# SCH_schematic-alarm_2025-03-28.net
KiCad netlist of a schematic drawn in EasyEDA
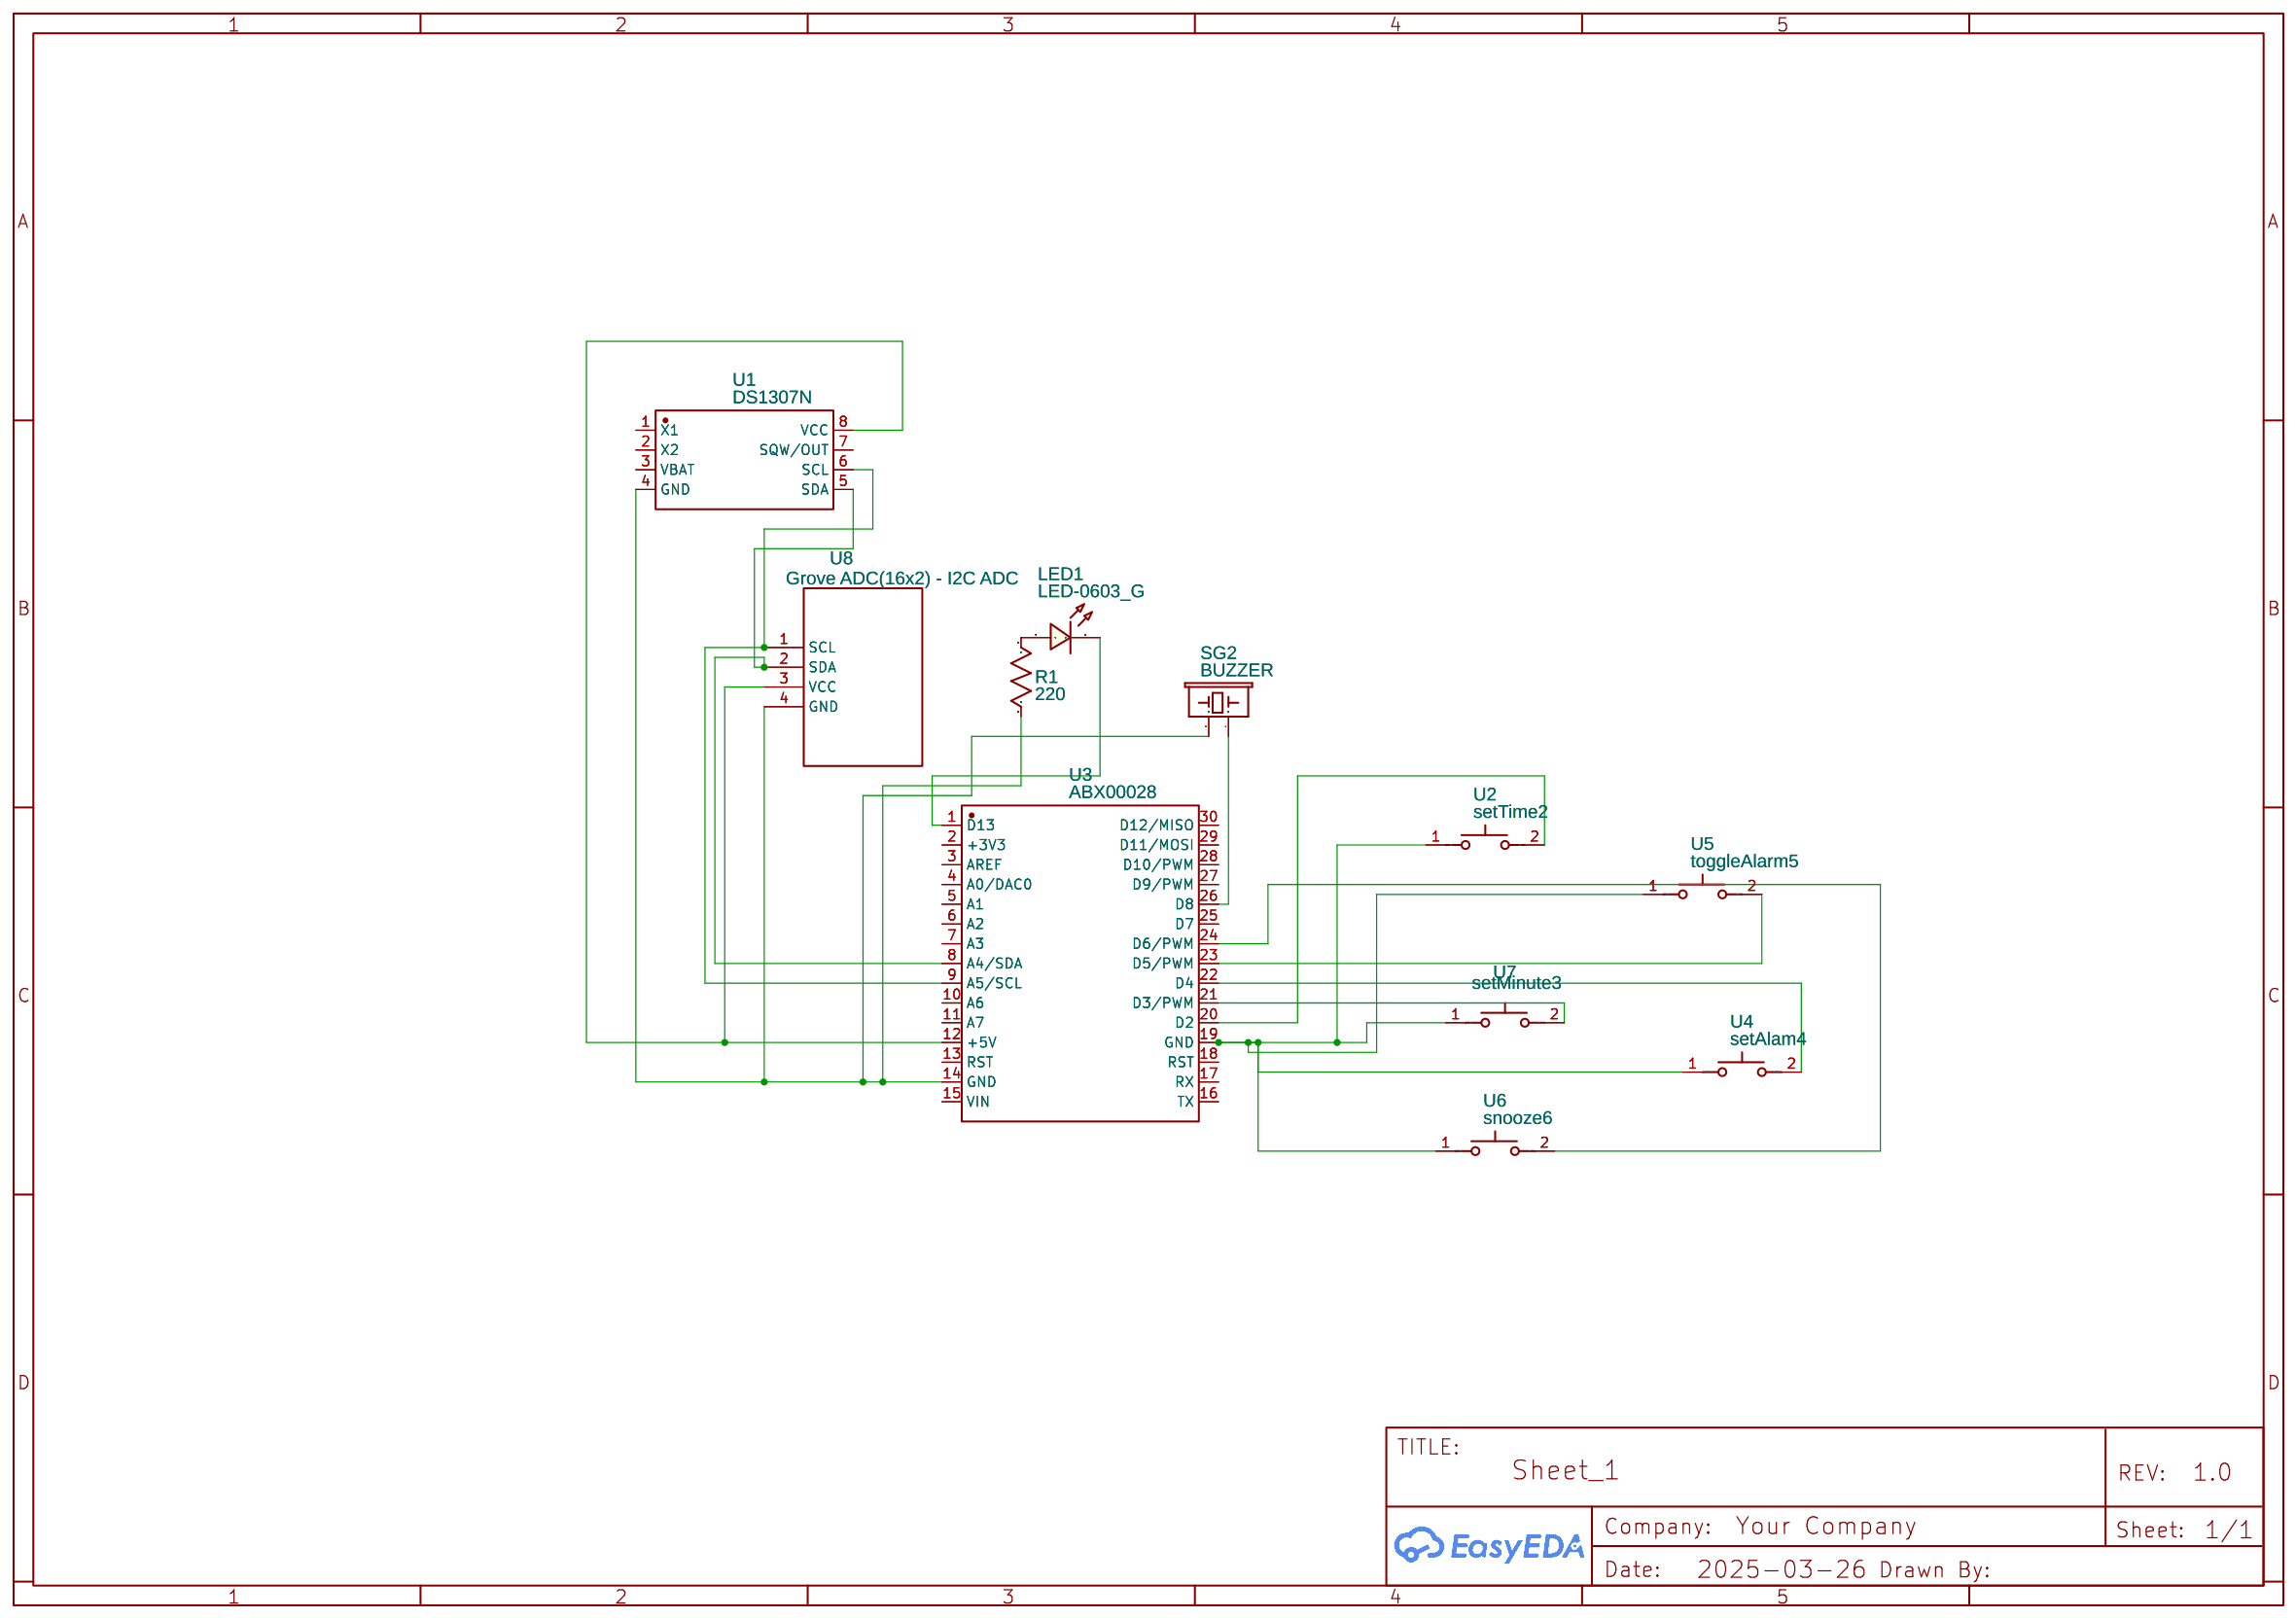
[diagram p0: schematic sheet]

(export (version "E")
  (design (tool "Eeschema 10.0.6"))
  (components
    (comp (ref "LED1")
      (value "LED-0603_G")
      (fields
        (field (name "Manufacturer Part") "19-217/GHC-YR1S2/3T")
        (field (name "Manufacturer") "EVERLIGHT(台湾亿光)")
      )
      (libsource (lib "") (part "LED-0603_G"))
    )
    (comp (ref "R1") (value "220") (libsource (lib "") (part "R_0603_US")))
    (comp (ref "SG2") (value "BUZZER") (libsource (lib "") (part "BUZZER")))
    (comp (ref "U1")
      (value "DS1307N")
      (fields (field (name "Manufacturer") "HGSEMI(华冠)"))
      (libsource (lib "") (part "DS1307N"))
    )
    (comp (ref "U2")
      (value "setTime2")
      (fields (field (name "Manufacturer Part") "BUTTON2"))
      (libsource (lib "") (part "BUTTON2"))
    )
    (comp (ref "U3")
      (value "ABX00028")
      (fields (field (name "Manufacturer") "arduino"))
      (libsource (lib "") (part "ABX00028"))
    )
    (comp (ref "U4")
      (value "setAlam4")
      (fields (field (name "Manufacturer Part") "BUTTON2"))
      (libsource (lib "") (part "BUTTON2"))
    )
    (comp (ref "U5")
      (value "toggleAlarm5")
      (fields (field (name "Manufacturer Part") "BUTTON2"))
      (libsource (lib "") (part "BUTTON2"))
    )
    (comp (ref "U6")
      (value "snooze6")
      (fields (field (name "Manufacturer Part") "BUTTON2"))
      (libsource (lib "") (part "BUTTON2"))
    )
    (comp (ref "U7")
      (value "setMinute3")
      (fields (field (name "Manufacturer Part") "BUTTON2"))
      (libsource (lib "") (part "BUTTON2"))
    )
    (comp (ref "U8") (value "Grove ADC(16x2) - I2C ADC") (libsource (lib "") (part "Grove - I2C ADC")))
  )
  (nets
    (net (code "1") (name "Net-(LED1-Pad1)") (class "Default")
      (node (ref "LED1") (pin "1") (pinfunction "1_1") (pintype "unspecified"))
      (node (ref "R1") (pin "1") (pinfunction "1_1") (pintype "unspecified"))
    )
    (net (code "2") (name "Net-(SG2-1)") (class "Default")
      (node (ref "R1") (pin "2") (pinfunction "2_2") (pintype "unspecified"))
      (node (ref "SG2") (pin "+") (pinfunction "1_+") (pintype "unspecified"))
      (node (ref "U1") (pin "4") (pinfunction "GND_4") (pintype "unspecified"))
      (node (ref "U3") (pin "14") (pinfunction "GND_14") (pintype "unspecified"))
      (node (ref "U8") (pin "4") (pinfunction "GND_4") (pintype "unspecified"))
    )
    (net (code "3") (name "Net-(SG2-2)") (class "Default")
      (node (ref "SG2") (pin "-") (pinfunction "2_-") (pintype "unspecified"))
      (node (ref "U3") (pin "26") (pinfunction "D8_26") (pintype "unspecified"))
    )
    (net (code "4") (name "Net-(U1-SCL)") (class "Default")
      (node (ref "U1") (pin "6") (pinfunction "SCL_6") (pintype "unspecified"))
      (node (ref "U3") (pin "9") (pinfunction "A5/SCL_9") (pintype "unspecified"))
      (node (ref "U8") (pin "1") (pinfunction "SCL_1") (pintype "unspecified"))
    )
    (net (code "5") (name "Net-(U1-SDA)") (class "Default")
      (node (ref "U1") (pin "5") (pinfunction "SDA_5") (pintype "unspecified"))
      (node (ref "U3") (pin "8") (pinfunction "A4/SDA_8") (pintype "unspecified"))
      (node (ref "U8") (pin "2") (pinfunction "SDA_2") (pintype "unspecified"))
    )
    (net (code "6") (name "Net-(U1-VCC)") (class "Default")
      (node (ref "U1") (pin "8") (pinfunction "VCC_8") (pintype "unspecified"))
      (node (ref "U3") (pin "12") (pinfunction "+5V_12") (pintype "unspecified"))
      (node (ref "U8") (pin "3") (pinfunction "VCC_3") (pintype "unspecified"))
    )
    (net (code "7") (name "Net-(U2-Pad1)") (class "Default")
      (node (ref "U2") (pin "1") (pinfunction "1_1") (pintype "unspecified"))
      (node (ref "U3") (pin "19") (pinfunction "GND_19") (pintype "unspecified"))
      (node (ref "U4") (pin "1") (pinfunction "1_1") (pintype "unspecified"))
      (node (ref "U5") (pin "1") (pinfunction "1_1") (pintype "unspecified"))
      (node (ref "U6") (pin "1") (pinfunction "1_1") (pintype "unspecified"))
      (node (ref "U7") (pin "1") (pinfunction "1_1") (pintype "unspecified"))
    )
    (net (code "8") (name "Net-(U3-D2)") (class "Default")
      (node (ref "U2") (pin "2") (pinfunction "2_2") (pintype "unspecified"))
      (node (ref "U3") (pin "20") (pinfunction "D2_20") (pintype "unspecified"))
    )
    (net (code "9") (name "Net-(U3-D3{slash}PWM)") (class "Default")
      (node (ref "U3") (pin "21") (pinfunction "D3/PWM_21") (pintype "unspecified"))
      (node (ref "U7") (pin "2") (pinfunction "2_2") (pintype "unspecified"))
    )
    (net (code "10") (name "Net-(U3-D4)") (class "Default")
      (node (ref "U3") (pin "22") (pinfunction "D4_22") (pintype "unspecified"))
      (node (ref "U4") (pin "2") (pinfunction "2_2") (pintype "unspecified"))
    )
    (net (code "11") (name "Net-(U3-D5{slash}PWM)") (class "Default")
      (node (ref "U3") (pin "23") (pinfunction "D5/PWM_23") (pintype "unspecified"))
      (node (ref "U5") (pin "2") (pinfunction "2_2") (pintype "unspecified"))
    )
    (net (code "12") (name "Net-(U3-D6{slash}PWM)") (class "Default")
      (node (ref "U3") (pin "24") (pinfunction "D6/PWM_24") (pintype "unspecified"))
      (node (ref "U6") (pin "2") (pinfunction "2_2") (pintype "unspecified"))
    )
    (net (code "13") (name "Net-(U3-D13)") (class "Default")
      (node (ref "LED1") (pin "2") (pinfunction "2_2") (pintype "unspecified"))
      (node (ref "U3") (pin "1") (pinfunction "D13_1") (pintype "unspecified"))
    )
    (net (code "14") (name "unconnected-(U1-SQW{slash}OUT-Pad7)") (class "Default")
      (node (ref "U1") (pin "7") (pinfunction "SQW/OUT_7") (pintype "unspecified"))
    )
    (net (code "15") (name "unconnected-(U1-VBAT-Pad3)") (class "Default")
      (node (ref "U1") (pin "3") (pinfunction "VBAT_3") (pintype "unspecified"))
    )
    (net (code "16") (name "unconnected-(U1-X1-Pad1)") (class "Default")
      (node (ref "U1") (pin "1") (pinfunction "X1_1") (pintype "unspecified"))
    )
    (net (code "17") (name "unconnected-(U1-X2-Pad2)") (class "Default")
      (node (ref "U1") (pin "2") (pinfunction "X2_2") (pintype "unspecified"))
    )
    (net (code "18") (name "unconnected-(U3-+3V3-Pad2)") (class "Default")
      (node (ref "U3") (pin "2") (pinfunction "+3V3_2") (pintype "unspecified"))
    )
    (net (code "19") (name "unconnected-(U3-A0{slash}DAC0-Pad4)") (class "Default")
      (node (ref "U3") (pin "4") (pinfunction "A0/DAC0_4") (pintype "unspecified"))
    )
    (net (code "20") (name "unconnected-(U3-A1-Pad5)") (class "Default")
      (node (ref "U3") (pin "5") (pinfunction "A1_5") (pintype "unspecified"))
    )
    (net (code "21") (name "unconnected-(U3-A2-Pad6)") (class "Default")
      (node (ref "U3") (pin "6") (pinfunction "A2_6") (pintype "unspecified"))
    )
    (net (code "22") (name "unconnected-(U3-A3-Pad7)") (class "Default")
      (node (ref "U3") (pin "7") (pinfunction "A3_7") (pintype "unspecified"))
    )
    (net (code "23") (name "unconnected-(U3-A6-Pad10)") (class "Default")
      (node (ref "U3") (pin "10") (pinfunction "A6_10") (pintype "unspecified"))
    )
    (net (code "24") (name "unconnected-(U3-A7-Pad11)") (class "Default")
      (node (ref "U3") (pin "11") (pinfunction "A7_11") (pintype "unspecified"))
    )
    (net (code "25") (name "unconnected-(U3-AREF-Pad3)") (class "Default")
      (node (ref "U3") (pin "3") (pinfunction "AREF_3") (pintype "unspecified"))
    )
    (net (code "26") (name "unconnected-(U3-D7-Pad25)") (class "Default")
      (node (ref "U3") (pin "25") (pinfunction "D7_25") (pintype "unspecified"))
    )
    (net (code "27") (name "unconnected-(U3-D9{slash}PWM-Pad27)") (class "Default")
      (node (ref "U3") (pin "27") (pinfunction "D9/PWM_27") (pintype "unspecified"))
    )
    (net (code "28") (name "unconnected-(U3-D10{slash}PWM-Pad28)") (class "Default")
      (node (ref "U3") (pin "28") (pinfunction "D10/PWM_28") (pintype "unspecified"))
    )
    (net (code "29") (name "unconnected-(U3-D11{slash}MOSI-Pad29)") (class "Default")
      (node (ref "U3") (pin "29") (pinfunction "D11/MOSI_29") (pintype "unspecified"))
    )
    (net (code "30") (name "unconnected-(U3-D12{slash}MISO-Pad30)") (class "Default")
      (node (ref "U3") (pin "30") (pinfunction "D12/MISO_30") (pintype "unspecified"))
    )
    (net (code "31") (name "unconnected-(U3-RST-Pad13)") (class "Default")
      (node (ref "U3") (pin "13") (pinfunction "RST_13") (pintype "unspecified"))
    )
    (net (code "32") (name "unconnected-(U3-RST-Pad18)") (class "Default")
      (node (ref "U3") (pin "18") (pinfunction "RST_18") (pintype "unspecified"))
    )
    (net (code "33") (name "unconnected-(U3-RX-Pad17)") (class "Default")
      (node (ref "U3") (pin "17") (pinfunction "RX_17") (pintype "unspecified"))
    )
    (net (code "34") (name "unconnected-(U3-TX-Pad16)") (class "Default")
      (node (ref "U3") (pin "16") (pinfunction "TX_16") (pintype "unspecified"))
    )
    (net (code "35") (name "unconnected-(U3-VIN-Pad15)") (class "Default")
      (node (ref "U3") (pin "15") (pinfunction "VIN_15") (pintype "unspecified"))
    )
  )
)
